# Tubes.net
KiCad netlist of a schematic drawn in EAGLE
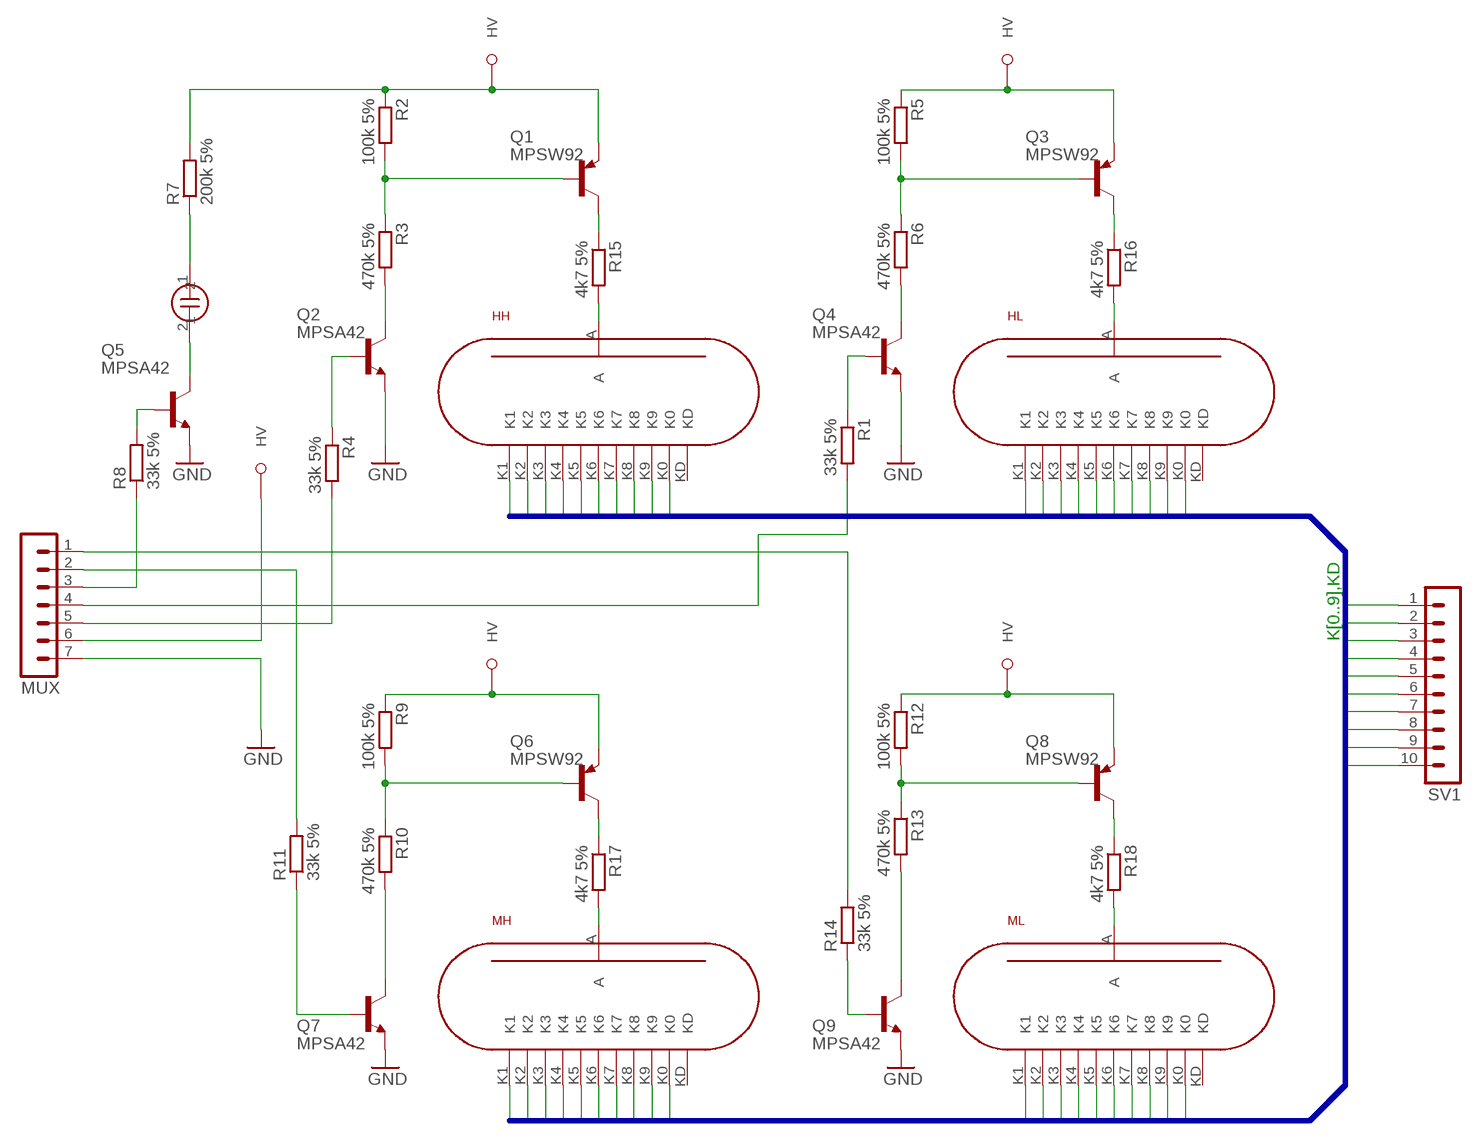
[diagram p0: schematic, sheet 1]

(export (version "E")
  (design (tool "Eeschema 10.0.6"))
  (components
    (comp (ref "HH")
      (value "LC531")
      (footprint "eagle-import:LC531")
      (libsource (lib "eagle-import") (part "LC531"))
    )
    (comp (ref "HL")
      (value "LC531")
      (footprint "eagle-import:LC531")
      (libsource (lib "eagle-import") (part "LC531"))
    )
    (comp (ref "MH")
      (value "LC531")
      (footprint "eagle-import:LC531")
      (libsource (lib "eagle-import") (part "LC531"))
    )
    (comp (ref "ML")
      (value "LC531")
      (footprint "eagle-import:LC531")
      (libsource (lib "eagle-import") (part "LC531"))
    )
    (comp (ref "MUX")
      (value "MA07-1")
      (footprint "eagle-import:MA07-1")
      (libsource (lib "eagle-import") (part "MA07-1"))
    )
    (comp (ref "NEON")
      (value "NEON")
      (footprint "eagle-import:NEON")
      (libsource (lib "eagle-import") (part "NEON"))
    )
    (comp (ref "Q1")
      (value "MPSW92")
      (footprint "eagle-import:TO92-CBE")
      (libsource (lib "eagle-import") (part "MPSW92"))
    )
    (comp (ref "Q2")
      (value "MPSA42")
      (footprint "eagle-import:TO92-CBE")
      (libsource (lib "eagle-import") (part "-NPN-TO92-CBEMPSA42"))
    )
    (comp (ref "Q3")
      (value "MPSW92")
      (footprint "eagle-import:TO92-CBE")
      (libsource (lib "eagle-import") (part "MPSW92"))
    )
    (comp (ref "Q4")
      (value "MPSA42")
      (footprint "eagle-import:TO92-CBE")
      (libsource (lib "eagle-import") (part "-NPN-TO92-CBEMPSA42"))
    )
    (comp (ref "Q5")
      (value "MPSA42")
      (footprint "eagle-import:TO92-CBE")
      (libsource (lib "eagle-import") (part "-NPN-TO92-CBEMPSA42"))
    )
    (comp (ref "Q6")
      (value "MPSW92")
      (footprint "eagle-import:TO92-CBE")
      (libsource (lib "eagle-import") (part "MPSW92"))
    )
    (comp (ref "Q7")
      (value "MPSA42")
      (footprint "eagle-import:TO92-CBE")
      (libsource (lib "eagle-import") (part "-NPN-TO92-CBEMPSA42"))
    )
    (comp (ref "Q8")
      (value "MPSW92")
      (footprint "eagle-import:TO92-CBE")
      (libsource (lib "eagle-import") (part "MPSW92"))
    )
    (comp (ref "Q9")
      (value "MPSA42")
      (footprint "eagle-import:TO92-CBE")
      (libsource (lib "eagle-import") (part "-NPN-TO92-CBEMPSA42"))
    )
    (comp (ref "R1")
      (value "33k 5%")
      (footprint "eagle-import:0204_5")
      (libsource (lib "eagle-import") (part "R-EU_0204/5"))
    )
    (comp (ref "R2")
      (value "100k 5%")
      (footprint "eagle-import:0204_5")
      (libsource (lib "eagle-import") (part "R-EU_0204/5"))
    )
    (comp (ref "R3")
      (value "470k 5%")
      (footprint "eagle-import:0204_5")
      (libsource (lib "eagle-import") (part "R-EU_0204/5"))
    )
    (comp (ref "R4")
      (value "33k 5%")
      (footprint "eagle-import:0204_5")
      (libsource (lib "eagle-import") (part "R-EU_0204/5"))
    )
    (comp (ref "R5")
      (value "100k 5%")
      (footprint "eagle-import:0204_5")
      (libsource (lib "eagle-import") (part "R-EU_0204/5"))
    )
    (comp (ref "R6")
      (value "470k 5%")
      (footprint "eagle-import:0204_5")
      (libsource (lib "eagle-import") (part "R-EU_0204/5"))
    )
    (comp (ref "R7")
      (value "200k 5%")
      (footprint "eagle-import:0204_5")
      (libsource (lib "eagle-import") (part "R-EU_0204/5"))
    )
    (comp (ref "R8")
      (value "33k 5%")
      (footprint "eagle-import:0204_5")
      (libsource (lib "eagle-import") (part "R-EU_0204/5"))
    )
    (comp (ref "R9")
      (value "100k 5%")
      (footprint "eagle-import:0204_5")
      (libsource (lib "eagle-import") (part "R-EU_0204/5"))
    )
    (comp (ref "R10")
      (value "470k 5%")
      (footprint "eagle-import:0204_5")
      (libsource (lib "eagle-import") (part "R-EU_0204/5"))
    )
    (comp (ref "R11")
      (value "33k 5%")
      (footprint "eagle-import:0204_5")
      (libsource (lib "eagle-import") (part "R-EU_0204/5"))
    )
    (comp (ref "R12")
      (value "100k 5%")
      (footprint "eagle-import:0204_5")
      (libsource (lib "eagle-import") (part "R-EU_0204/5"))
    )
    (comp (ref "R13")
      (value "470k 5%")
      (footprint "eagle-import:0204_5")
      (libsource (lib "eagle-import") (part "R-EU_0204/5"))
    )
    (comp (ref "R14")
      (value "33k 5%")
      (footprint "eagle-import:0204_5")
      (libsource (lib "eagle-import") (part "R-EU_0204/5"))
    )
    (comp (ref "R15")
      (value "4k7 5%")
      (footprint "eagle-import:0204_5")
      (libsource (lib "eagle-import") (part "R-EU_0204/5"))
    )
    (comp (ref "R16")
      (value "4k7 5%")
      (footprint "eagle-import:0204_5")
      (libsource (lib "eagle-import") (part "R-EU_0204/5"))
    )
    (comp (ref "R17")
      (value "4k7 5%")
      (footprint "eagle-import:0204_5")
      (libsource (lib "eagle-import") (part "R-EU_0204/5"))
    )
    (comp (ref "R18")
      (value "4k7 5%")
      (footprint "eagle-import:0204_5")
      (libsource (lib "eagle-import") (part "R-EU_0204/5"))
    )
    (comp (ref "SV1")
      (value "MA10-1")
      (footprint "eagle-import:MA10-1")
      (libsource (lib "eagle-import") (part "MA10-1"))
    )
  )
  (nets
    (net (code "1") (name "/K0") (class "Default")
      (node (ref "HH") (pin "K0") (pinfunction "K0_K0") (pintype "bidirectional"))
      (node (ref "HL") (pin "K0") (pinfunction "K0_K0") (pintype "bidirectional"))
      (node (ref "MH") (pin "K0") (pinfunction "K0_K0") (pintype "bidirectional"))
      (node (ref "ML") (pin "K0") (pinfunction "K0_K0") (pintype "bidirectional"))
      (node (ref "SV1") (pin "3") (pinfunction "3_3") (pintype "passive"))
    )
    (net (code "2") (name "/K1") (class "Default")
      (node (ref "HH") (pin "K1") (pinfunction "K1_K1") (pintype "bidirectional"))
      (node (ref "HL") (pin "K1") (pinfunction "K1_K1") (pintype "bidirectional"))
      (node (ref "MH") (pin "K1") (pinfunction "K1_K1") (pintype "bidirectional"))
      (node (ref "ML") (pin "K1") (pinfunction "K1_K1") (pintype "bidirectional"))
      (node (ref "SV1") (pin "1") (pinfunction "1_1") (pintype "passive"))
    )
    (net (code "3") (name "/K2") (class "Default")
      (node (ref "HH") (pin "K2") (pinfunction "K2_K2") (pintype "bidirectional"))
      (node (ref "HL") (pin "K2") (pinfunction "K2_K2") (pintype "bidirectional"))
      (node (ref "MH") (pin "K2") (pinfunction "K2_K2") (pintype "bidirectional"))
      (node (ref "ML") (pin "K2") (pinfunction "K2_K2") (pintype "bidirectional"))
      (node (ref "SV1") (pin "2") (pinfunction "2_2") (pintype "passive"))
    )
    (net (code "4") (name "/K3") (class "Default")
      (node (ref "HH") (pin "K3") (pinfunction "K3_K3") (pintype "bidirectional"))
      (node (ref "HL") (pin "K3") (pinfunction "K3_K3") (pintype "bidirectional"))
      (node (ref "MH") (pin "K3") (pinfunction "K3_K3") (pintype "bidirectional"))
      (node (ref "ML") (pin "K3") (pinfunction "K3_K3") (pintype "bidirectional"))
      (node (ref "SV1") (pin "4") (pinfunction "4_4") (pintype "passive"))
    )
    (net (code "5") (name "/K4") (class "Default")
      (node (ref "HH") (pin "K4") (pinfunction "K4_K4") (pintype "bidirectional"))
      (node (ref "HL") (pin "K4") (pinfunction "K4_K4") (pintype "bidirectional"))
      (node (ref "MH") (pin "K4") (pinfunction "K4_K4") (pintype "bidirectional"))
      (node (ref "ML") (pin "K4") (pinfunction "K4_K4") (pintype "bidirectional"))
      (node (ref "SV1") (pin "6") (pinfunction "6_6") (pintype "passive"))
    )
    (net (code "6") (name "/K5") (class "Default")
      (node (ref "HH") (pin "K5") (pinfunction "K5_K5") (pintype "bidirectional"))
      (node (ref "HL") (pin "K5") (pinfunction "K5_K5") (pintype "bidirectional"))
      (node (ref "MH") (pin "K5") (pinfunction "K5_K5") (pintype "bidirectional"))
      (node (ref "ML") (pin "K5") (pinfunction "K5_K5") (pintype "bidirectional"))
      (node (ref "SV1") (pin "8") (pinfunction "8_8") (pintype "passive"))
    )
    (net (code "7") (name "/K6") (class "Default")
      (node (ref "HH") (pin "K6") (pinfunction "K6_K6") (pintype "bidirectional"))
      (node (ref "HL") (pin "K6") (pinfunction "K6_K6") (pintype "bidirectional"))
      (node (ref "MH") (pin "K6") (pinfunction "K6_K6") (pintype "bidirectional"))
      (node (ref "ML") (pin "K6") (pinfunction "K6_K6") (pintype "bidirectional"))
      (node (ref "SV1") (pin "10") (pinfunction "10_10") (pintype "passive"))
    )
    (net (code "8") (name "/K7") (class "Default")
      (node (ref "HH") (pin "K7") (pinfunction "K7_K7") (pintype "bidirectional"))
      (node (ref "HL") (pin "K7") (pinfunction "K7_K7") (pintype "bidirectional"))
      (node (ref "MH") (pin "K7") (pinfunction "K7_K7") (pintype "bidirectional"))
      (node (ref "ML") (pin "K7") (pinfunction "K7_K7") (pintype "bidirectional"))
      (node (ref "SV1") (pin "9") (pinfunction "9_9") (pintype "passive"))
    )
    (net (code "9") (name "/K8") (class "Default")
      (node (ref "HH") (pin "K8") (pinfunction "K8_K8") (pintype "bidirectional"))
      (node (ref "HL") (pin "K8") (pinfunction "K8_K8") (pintype "bidirectional"))
      (node (ref "MH") (pin "K8") (pinfunction "K8_K8") (pintype "bidirectional"))
      (node (ref "ML") (pin "K8") (pinfunction "K8_K8") (pintype "bidirectional"))
      (node (ref "SV1") (pin "7") (pinfunction "7_7") (pintype "passive"))
    )
    (net (code "10") (name "/K9") (class "Default")
      (node (ref "HH") (pin "K9") (pinfunction "K9_K9") (pintype "bidirectional"))
      (node (ref "HL") (pin "K9") (pinfunction "K9_K9") (pintype "bidirectional"))
      (node (ref "MH") (pin "K9") (pinfunction "K9_K9") (pintype "bidirectional"))
      (node (ref "ML") (pin "K9") (pinfunction "K9_K9") (pintype "bidirectional"))
      (node (ref "SV1") (pin "5") (pinfunction "5_5") (pintype "passive"))
    )
    (net (code "11") (name "GND") (class "Default")
      (node (ref "MUX") (pin "7") (pinfunction "7_7") (pintype "passive"))
      (node (ref "Q2") (pin "E") (pinfunction "E_E") (pintype "passive"))
      (node (ref "Q4") (pin "E") (pinfunction "E_E") (pintype "passive"))
      (node (ref "Q5") (pin "E") (pinfunction "E_E") (pintype "passive"))
      (node (ref "Q7") (pin "E") (pinfunction "E_E") (pintype "passive"))
      (node (ref "Q9") (pin "E") (pinfunction "E_E") (pintype "passive"))
    )
    (net (code "12") (name "HV") (class "Default")
      (node (ref "MUX") (pin "6") (pinfunction "6_6") (pintype "passive"))
      (node (ref "Q1") (pin "E") (pinfunction "E_E") (pintype "passive"))
      (node (ref "Q3") (pin "E") (pinfunction "E_E") (pintype "passive"))
      (node (ref "Q6") (pin "E") (pinfunction "E_E") (pintype "passive"))
      (node (ref "Q8") (pin "E") (pinfunction "E_E") (pintype "passive"))
      (node (ref "R12") (pin "1") (pinfunction "1_1") (pintype "passive"))
      (node (ref "R2") (pin "1") (pinfunction "1_1") (pintype "passive"))
      (node (ref "R5") (pin "1") (pinfunction "1_1") (pintype "passive"))
      (node (ref "R7") (pin "2") (pinfunction "2_2") (pintype "passive"))
      (node (ref "R9") (pin "1") (pinfunction "1_1") (pintype "passive"))
    )
    (net (code "13") (name "Net-(HH-PadA)") (class "Default")
      (node (ref "HH") (pin "A") (pinfunction "A_A") (pintype "bidirectional"))
      (node (ref "R15") (pin "2") (pinfunction "2_2") (pintype "passive"))
    )
    (net (code "14") (name "Net-(HL-PadA)") (class "Default")
      (node (ref "HL") (pin "A") (pinfunction "A_A") (pintype "bidirectional"))
      (node (ref "R16") (pin "2") (pinfunction "2_2") (pintype "passive"))
    )
    (net (code "15") (name "Net-(MH-PadA)") (class "Default")
      (node (ref "MH") (pin "A") (pinfunction "A_A") (pintype "bidirectional"))
      (node (ref "R17") (pin "2") (pinfunction "2_2") (pintype "passive"))
    )
    (net (code "16") (name "Net-(ML-PadA)") (class "Default")
      (node (ref "ML") (pin "A") (pinfunction "A_A") (pintype "bidirectional"))
      (node (ref "R18") (pin "2") (pinfunction "2_2") (pintype "passive"))
    )
    (net (code "17") (name "Net-(MUX-Pad1)") (class "Default")
      (node (ref "MUX") (pin "1") (pinfunction "1_1") (pintype "passive"))
      (node (ref "R14") (pin "2") (pinfunction "2_2") (pintype "passive"))
    )
    (net (code "18") (name "Net-(MUX-Pad2)") (class "Default")
      (node (ref "MUX") (pin "2") (pinfunction "2_2") (pintype "passive"))
      (node (ref "R11") (pin "2") (pinfunction "2_2") (pintype "passive"))
    )
    (net (code "19") (name "Net-(MUX-Pad3)") (class "Default")
      (node (ref "MUX") (pin "3") (pinfunction "3_3") (pintype "passive"))
      (node (ref "R8") (pin "1") (pinfunction "1_1") (pintype "passive"))
    )
    (net (code "20") (name "Net-(MUX-Pad4)") (class "Default")
      (node (ref "MUX") (pin "4") (pinfunction "4_4") (pintype "passive"))
      (node (ref "R1") (pin "2") (pinfunction "2_2") (pintype "passive"))
    )
    (net (code "21") (name "Net-(MUX-Pad5)") (class "Default")
      (node (ref "MUX") (pin "5") (pinfunction "5_5") (pintype "passive"))
      (node (ref "R4") (pin "2") (pinfunction "2_2") (pintype "passive"))
    )
    (net (code "22") (name "Net-(NEON-Pad1)") (class "Default")
      (node (ref "NEON") (pin "1") (pinfunction "1_1") (pintype "bidirectional"))
      (node (ref "R7") (pin "1") (pinfunction "1_1") (pintype "passive"))
    )
    (net (code "23") (name "Net-(NEON-Pad2)") (class "Default")
      (node (ref "NEON") (pin "2") (pinfunction "2_2") (pintype "bidirectional"))
      (node (ref "Q5") (pin "C") (pinfunction "C_C") (pintype "passive"))
    )
    (net (code "24") (name "Net-(Q1-PadB)") (class "Default")
      (node (ref "Q1") (pin "B") (pinfunction "B_B") (pintype "passive"))
      (node (ref "R2") (pin "2") (pinfunction "2_2") (pintype "passive"))
      (node (ref "R3") (pin "1") (pinfunction "1_1") (pintype "passive"))
    )
    (net (code "25") (name "Net-(Q1-PadC)") (class "Default")
      (node (ref "Q1") (pin "C") (pinfunction "C_C") (pintype "passive"))
      (node (ref "R15") (pin "1") (pinfunction "1_1") (pintype "passive"))
    )
    (net (code "26") (name "Net-(Q2-PadB)") (class "Default")
      (node (ref "Q2") (pin "B") (pinfunction "B_B") (pintype "passive"))
      (node (ref "R4") (pin "1") (pinfunction "1_1") (pintype "passive"))
    )
    (net (code "27") (name "Net-(Q2-PadC)") (class "Default")
      (node (ref "Q2") (pin "C") (pinfunction "C_C") (pintype "passive"))
      (node (ref "R3") (pin "2") (pinfunction "2_2") (pintype "passive"))
    )
    (net (code "28") (name "Net-(Q3-PadB)") (class "Default")
      (node (ref "Q3") (pin "B") (pinfunction "B_B") (pintype "passive"))
      (node (ref "R5") (pin "2") (pinfunction "2_2") (pintype "passive"))
      (node (ref "R6") (pin "1") (pinfunction "1_1") (pintype "passive"))
    )
    (net (code "29") (name "Net-(Q3-PadC)") (class "Default")
      (node (ref "Q3") (pin "C") (pinfunction "C_C") (pintype "passive"))
      (node (ref "R16") (pin "1") (pinfunction "1_1") (pintype "passive"))
    )
    (net (code "30") (name "Net-(Q4-PadB)") (class "Default")
      (node (ref "Q4") (pin "B") (pinfunction "B_B") (pintype "passive"))
      (node (ref "R1") (pin "1") (pinfunction "1_1") (pintype "passive"))
    )
    (net (code "31") (name "Net-(Q4-PadC)") (class "Default")
      (node (ref "Q4") (pin "C") (pinfunction "C_C") (pintype "passive"))
      (node (ref "R6") (pin "2") (pinfunction "2_2") (pintype "passive"))
    )
    (net (code "32") (name "Net-(Q5-PadB)") (class "Default")
      (node (ref "Q5") (pin "B") (pinfunction "B_B") (pintype "passive"))
      (node (ref "R8") (pin "2") (pinfunction "2_2") (pintype "passive"))
    )
    (net (code "33") (name "Net-(Q6-PadB)") (class "Default")
      (node (ref "Q6") (pin "B") (pinfunction "B_B") (pintype "passive"))
      (node (ref "R10") (pin "1") (pinfunction "1_1") (pintype "passive"))
      (node (ref "R9") (pin "2") (pinfunction "2_2") (pintype "passive"))
    )
    (net (code "34") (name "Net-(Q6-PadC)") (class "Default")
      (node (ref "Q6") (pin "C") (pinfunction "C_C") (pintype "passive"))
      (node (ref "R17") (pin "1") (pinfunction "1_1") (pintype "passive"))
    )
    (net (code "35") (name "Net-(Q7-PadB)") (class "Default")
      (node (ref "Q7") (pin "B") (pinfunction "B_B") (pintype "passive"))
      (node (ref "R11") (pin "1") (pinfunction "1_1") (pintype "passive"))
    )
    (net (code "36") (name "Net-(Q7-PadC)") (class "Default")
      (node (ref "Q7") (pin "C") (pinfunction "C_C") (pintype "passive"))
      (node (ref "R10") (pin "2") (pinfunction "2_2") (pintype "passive"))
    )
    (net (code "37") (name "Net-(Q8-PadB)") (class "Default")
      (node (ref "Q8") (pin "B") (pinfunction "B_B") (pintype "passive"))
      (node (ref "R12") (pin "2") (pinfunction "2_2") (pintype "passive"))
      (node (ref "R13") (pin "1") (pinfunction "1_1") (pintype "passive"))
    )
    (net (code "38") (name "Net-(Q8-PadC)") (class "Default")
      (node (ref "Q8") (pin "C") (pinfunction "C_C") (pintype "passive"))
      (node (ref "R18") (pin "1") (pinfunction "1_1") (pintype "passive"))
    )
    (net (code "39") (name "Net-(Q9-PadB)") (class "Default")
      (node (ref "Q9") (pin "B") (pinfunction "B_B") (pintype "passive"))
      (node (ref "R14") (pin "1") (pinfunction "1_1") (pintype "passive"))
    )
    (net (code "40") (name "Net-(Q9-PadC)") (class "Default")
      (node (ref "Q9") (pin "C") (pinfunction "C_C") (pintype "passive"))
      (node (ref "R13") (pin "2") (pinfunction "2_2") (pintype "passive"))
    )
    (net (code "41") (name "unconnected-(HH-PadKD)") (class "Default")
      (node (ref "HH") (pin "KD") (pinfunction "KD_KD") (pintype "bidirectional"))
    )
    (net (code "42") (name "unconnected-(HL-PadKD)") (class "Default")
      (node (ref "HL") (pin "KD") (pinfunction "KD_KD") (pintype "bidirectional"))
    )
    (net (code "43") (name "unconnected-(MH-PadKD)") (class "Default")
      (node (ref "MH") (pin "KD") (pinfunction "KD_KD") (pintype "bidirectional"))
    )
    (net (code "44") (name "unconnected-(ML-PadKD)") (class "Default")
      (node (ref "ML") (pin "KD") (pinfunction "KD_KD") (pintype "bidirectional"))
    )
  )
)
